# IDEAL_DIODE_2.net
KiCad netlist of a schematic drawn in Altium Designer
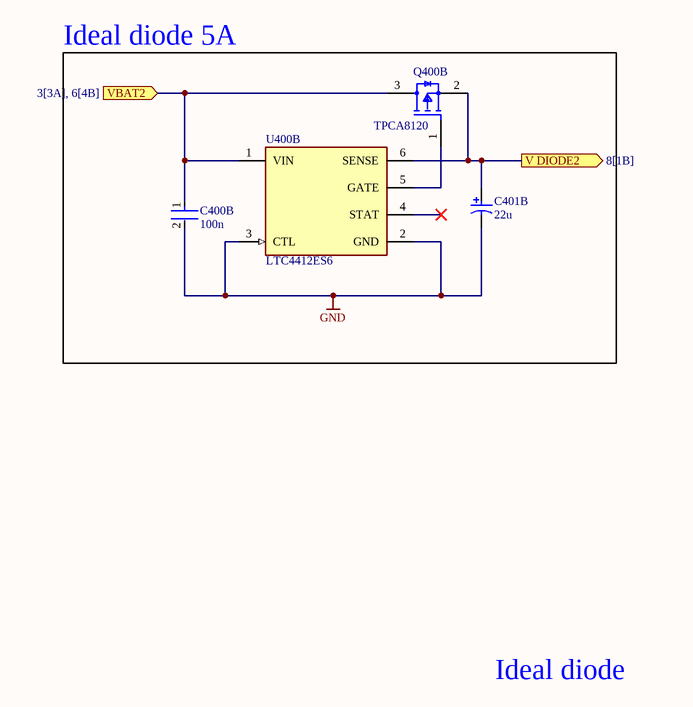
[diagram p0: IDEAL_DIODE_2.SchDoc]

(export (version "E")
  (design (tool "Eeschema 10.0.6"))
  (components
    (comp (ref "C400B")
      (value "100n")
      (footprint "FP-0603-L_1_6_0_15-W_0_81-IPC_A")
      (description "Automotive Ceramic Capacitor, 0603, 100nF, 10%, X7R, 15%, 50V")
      (fields (field (name "VOLTAGE") "50V") (field (name "TOLERANCE") "10%"))
      (libsource (lib "Altium Content Vault") (part "02cd4be3c70576c341d710602a673aa"))
    )
    (comp (ref "C401B")
      (value "22u")
      (footprint "KEMT-T491-B_L")
      (description "Tantalum Capacitor, 22 uF, +/- 10%, 10 V, -55 to 125 degC, 2-Pin SMD, RoHS, Tape and Reel")
      (fields (field (name "VOLTAGE") "10VDC") (field (name "MANUFACTURER") "Kemet"))
      (libsource (lib "Altium Content Vault") (part "CAP-P-2"))
    )
    (comp (ref "Q400B")
      (value "TPCA8120")
      (footprint "FP-527AG-MFG")
      (description "MOSFET P-CH 20V 2A SSOT3")
      (libsource (lib "Altium Content Vault") (part "d23f43cc42f60b967b7caccf14518fd"))
    )
    (comp (ref "U400B")
      (value "LTC4412ES6")
      (footprint "FP-S6-6-05-08-1636-IPC_C")
      (description "IC OR CTRLR SRC SELECT TSOT23-6")
      (libsource (lib "Altium Content Vault") (part "07cb0f4431a3a7488227ca1baae77bb"))
    )
  )
  (nets
    (net (code "1") (name "/V DIODE2") (class "Default")
      (node (ref "C401B") (pin "1") (pinfunction "1_1") (pintype "passive"))
      (node (ref "Q400B") (pin "2") (pinfunction "S_2") (pintype "passive"))
      (node (ref "U400B") (pin "6") (pinfunction "SENSE_6") (pintype "passive"))
    )
    (net (code "2") (name "/VBAT2") (class "Default")
      (node (ref "C400B") (pin "1") (pinfunction "1_1") (pintype "passive"))
      (node (ref "Q400B") (pin "3") (pinfunction "D_3") (pintype "passive"))
      (node (ref "U400B") (pin "1") (pinfunction "VIN_1") (pintype "power_in"))
    )
    (net (code "3") (name "GND") (class "Default")
      (node (ref "C400B") (pin "2") (pinfunction "2_2") (pintype "passive"))
      (node (ref "C401B") (pin "2") (pinfunction "2_2") (pintype "passive"))
      (node (ref "U400B") (pin "2") (pinfunction "GND_2") (pintype "power_in"))
      (node (ref "U400B") (pin "3") (pinfunction "CTL_3") (pintype "input"))
    )
    (net (code "4") (name "Net-(Q400B-G)") (class "Default")
      (node (ref "Q400B") (pin "1") (pinfunction "G_1") (pintype "passive"))
      (node (ref "U400B") (pin "5") (pinfunction "GATE_5") (pintype "passive"))
    )
    (net (code "5") (name "unconnected-(U400B-STAT-Pad4)") (class "Default")
      (node (ref "U400B") (pin "4") (pinfunction "STAT_4") (pintype "open_collector+no_connect"))
    )
  )
)
